# 4_PWM_MOSFETs.net
KiCad netlist of a schematic drawn in Altium Designer
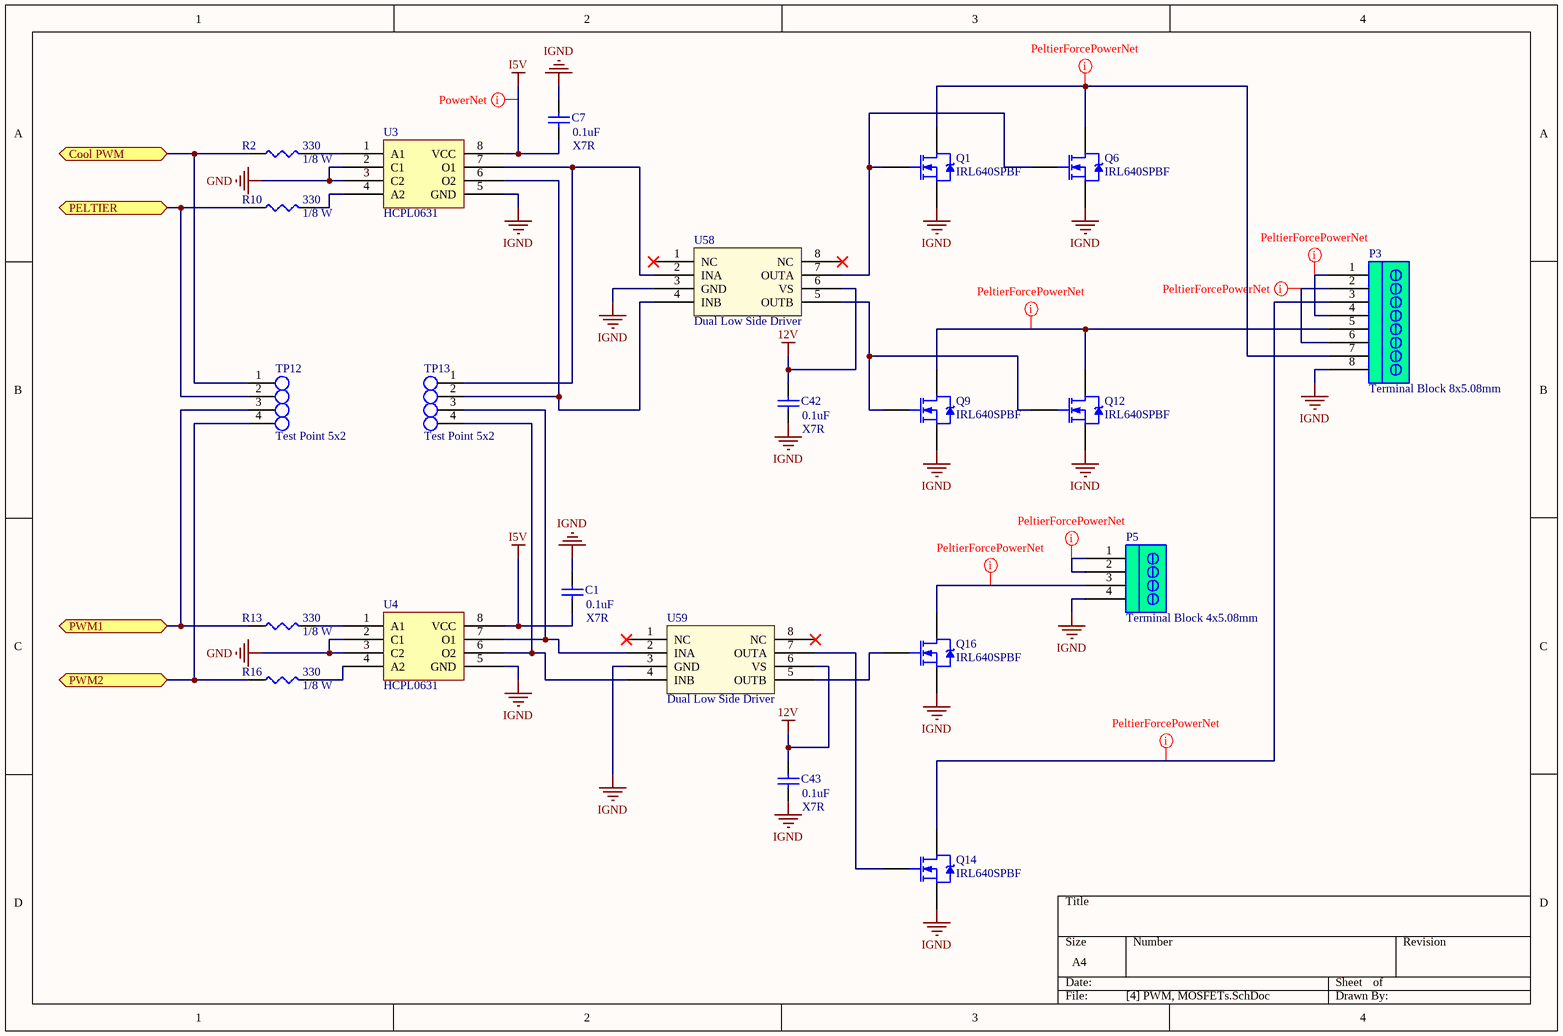
[diagram p0: [4] PWM, MOSFETs.SchDoc]

(export (version "E")
  (design (tool "Eeschema 10.0.6"))
  (components
    (comp (ref "C1")
      (value "0.1uF")
      (footprint "CAP0805")
      (description "Surface-mount ceramic multilayer capacitor")
      (fields (field (name "VOLTAGE") "50V") (field (name "TOLERANCE") "5%") (field (name "TYPE") "X7R"))
      (libsource (lib "Capacitors") (part "CAP0805 0.1uF X7R"))
    )
    (comp (ref "C7")
      (value "0.1uF")
      (footprint "CAP0805")
      (description "Surface-mount ceramic multilayer capacitor")
      (fields (field (name "VOLTAGE") "50V") (field (name "TOLERANCE") "5%") (field (name "TYPE") "X7R"))
      (libsource (lib "Capacitors") (part "CAP0805 0.1uF X7R"))
    )
    (comp (ref "C42")
      (value "0.1uF")
      (footprint "CAP0805")
      (description "Surface-mount ceramic multilayer capacitor")
      (fields (field (name "VOLTAGE") "50V") (field (name "TOLERANCE") "5%") (field (name "TYPE") "X7R"))
      (libsource (lib "Capacitors") (part "CAP0805 0.1uF X7R"))
    )
    (comp (ref "C43")
      (value "0.1uF")
      (footprint "CAP0805")
      (description "Surface-mount ceramic multilayer capacitor")
      (fields (field (name "VOLTAGE") "50V") (field (name "TOLERANCE") "5%") (field (name "TYPE") "X7R"))
      (libsource (lib "Capacitors") (part "CAP0805 0.1uF X7R"))
    )
    (comp (ref "P3")
      (value "Terminal Block 8x5.08mm")
      (footprint "SOCKET 8x5.08")
      (description "Terminal Block Socket Right Angle 8x5.08mm 2-Wall")
      (libsource (lib "IndustrialConnectors") (part "Socket_8x5.08_RA_2Wall"))
    )
    (comp (ref "P5")
      (value "Terminal Block 4x5.08mm")
      (footprint "Socket 4x5.08")
      (description "Terminal Block Socket Right Angle 4x5.08mm 2-Wall")
      (libsource (lib "IndustrialConnectors") (part "Socket_4x5.08_RA_2Wall"))
    )
    (comp (ref "Q1")
      (value "IRL640SPBF")
      (footprint "TO-263AB")
      (description "HEXFET N-Channel Power MOSFET")
      (fields (field (name "MANUFACTURER") "Vishay"))
      (libsource (lib "BJT") (part "IRL640SPBF"))
    )
    (comp (ref "Q6")
      (value "IRL640SPBF")
      (footprint "TO-263AB")
      (description "HEXFET N-Channel Power MOSFET")
      (fields (field (name "MANUFACTURER") "Vishay"))
      (libsource (lib "BJT") (part "IRL640SPBF"))
    )
    (comp (ref "Q9")
      (value "IRL640SPBF")
      (footprint "TO-263AB")
      (description "HEXFET N-Channel Power MOSFET")
      (fields (field (name "MANUFACTURER") "Vishay"))
      (libsource (lib "BJT") (part "IRL640SPBF"))
    )
    (comp (ref "Q12")
      (value "IRL640SPBF")
      (footprint "TO-263AB")
      (description "HEXFET N-Channel Power MOSFET")
      (fields (field (name "MANUFACTURER") "Vishay"))
      (libsource (lib "BJT") (part "IRL640SPBF"))
    )
    (comp (ref "Q14")
      (value "IRL640SPBF")
      (footprint "TO-263AB")
      (description "HEXFET N-Channel Power MOSFET")
      (fields (field (name "MANUFACTURER") "Vishay"))
      (libsource (lib "BJT") (part "IRL640SPBF"))
    )
    (comp (ref "Q16")
      (value "IRL640SPBF")
      (footprint "TO-263AB")
      (description "HEXFET N-Channel Power MOSFET")
      (fields (field (name "MANUFACTURER") "Vishay"))
      (libsource (lib "BJT") (part "IRL640SPBF"))
    )
    (comp (ref "R2")
      (value "330")
      (footprint "RES0805")
      (description "Think Film Chip resistor")
      (fields
        (field (name "TOLERANCE") "1%")
        (field (name "MANUFACTURER PART NUMBER") "RC0805FR-07330RL")
        (field (name "RATING") "1/8 W")
      )
      (libsource (lib "Resistors") (part "RES0805 330R 1%"))
    )
    (comp (ref "R10")
      (value "330")
      (footprint "RES0805")
      (description "Think Film Chip resistor")
      (fields
        (field (name "TOLERANCE") "1%")
        (field (name "MANUFACTURER PART NUMBER") "RC0805FR-07330RL")
        (field (name "RATING") "1/8 W")
      )
      (libsource (lib "Resistors") (part "RES0805 330R 1%"))
    )
    (comp (ref "R13")
      (value "330")
      (footprint "RES0805")
      (description "Think Film Chip resistor")
      (fields
        (field (name "TOLERANCE") "1%")
        (field (name "MANUFACTURER PART NUMBER") "RC0805FR-07330RL")
        (field (name "RATING") "1/8 W")
      )
      (libsource (lib "Resistors") (part "RES0805 330R 1%"))
    )
    (comp (ref "R16")
      (value "330")
      (footprint "RES0805")
      (description "Think Film Chip resistor")
      (fields
        (field (name "TOLERANCE") "1%")
        (field (name "MANUFACTURER PART NUMBER") "RC0805FR-07330RL")
        (field (name "RATING") "1/8 W")
      )
      (libsource (lib "Resistors") (part "RES0805 330R 1%"))
    )
    (comp (ref "TP12")
      (value "Test Point 5x2")
      (footprint "PG-1.5-13.5-4P-2.54PH")
      (libsource (lib "Connectors") (part "PG-1.5-13.5-4P-2.54PH"))
    )
    (comp (ref "TP13")
      (value "Test Point 5x2")
      (footprint "PG-1.5-13.5-4P-2.54PH")
      (libsource (lib "Connectors") (part "PG-1.5-13.5-4P-2.54PH"))
    )
    (comp (ref "U3")
      (value "HCPL0631")
      (footprint "SOIC8")
      (description "2-channel opto-coupler")
      (libsource (lib "Avago Optocouplers") (part "HCPL0631"))
    )
    (comp (ref "U4")
      (value "HCPL0631")
      (footprint "SOIC8")
      (description "2-channel opto-coupler")
      (libsource (lib "Avago Optocouplers") (part "HCPL0631"))
    )
    (comp (ref "U58")
      (value "Dual Low Side Driver")
      (footprint "SOIC8")
      (description "IR MOSFET Dual Low Side Driver")
      (fields (field (name "MANUFACTURER") "IR") (field (name "MANUFACTURER PART NUMBER") "IR4426"))
      (libsource (lib "IR MOSFET Driver") (part "IR4426"))
    )
    (comp (ref "U59")
      (value "Dual Low Side Driver")
      (footprint "SOIC8")
      (description "IR MOSFET Dual Low Side Driver")
      (fields (field (name "MANUFACTURER") "IR") (field (name "MANUFACTURER PART NUMBER") "IR4426"))
      (libsource (lib "IR MOSFET Driver") (part "IR4426"))
    )
  )
  (nets
    (net (code "1") (name "/Cool PWM") (class "Default")
      (node (ref "R2") (pin "1") (pintype "passive"))
      (node (ref "TP12") (pin "1") (pinfunction "1_1") (pintype "passive"))
    )
    (net (code "2") (name "/PELTIER") (class "Default")
      (node (ref "R10") (pin "1") (pintype "passive"))
      (node (ref "TP12") (pin "2") (pinfunction "2_2") (pintype "passive"))
    )
    (net (code "3") (name "/PWM1") (class "Default")
      (node (ref "R13") (pin "1") (pintype "passive"))
      (node (ref "TP12") (pin "3") (pinfunction "3_3") (pintype "passive"))
    )
    (net (code "4") (name "/PWM2") (class "Default")
      (node (ref "R16") (pin "1") (pintype "passive"))
      (node (ref "TP12") (pin "4") (pinfunction "4_4") (pintype "passive"))
    )
    (net (code "5") (name "12V") (class "Default")
      (node (ref "C42") (pin "2") (pinfunction "2_2") (pintype "passive"))
      (node (ref "C43") (pin "2") (pinfunction "2_2") (pintype "passive"))
      (node (ref "U58") (pin "6") (pinfunction "VS_6") (pintype "passive"))
      (node (ref "U59") (pin "6") (pinfunction "VS_6") (pintype "passive"))
    )
    (net (code "6") (name "GND") (class "Default")
      (node (ref "U3") (pin "2") (pinfunction "C1_2") (pintype "passive"))
      (node (ref "U3") (pin "3") (pinfunction "C2_3") (pintype "passive"))
      (node (ref "U4") (pin "2") (pinfunction "C1_2") (pintype "passive"))
      (node (ref "U4") (pin "3") (pinfunction "C2_3") (pintype "passive"))
    )
    (net (code "7") (name "I5V") (class "Default")
      (node (ref "C1") (pin "1") (pinfunction "1_1") (pintype "passive"))
      (node (ref "C7") (pin "1") (pinfunction "1_1") (pintype "passive"))
      (node (ref "U3") (pin "8") (pinfunction "VCC_8") (pintype "passive"))
      (node (ref "U4") (pin "8") (pinfunction "VCC_8") (pintype "passive"))
    )
    (net (code "8") (name "IGND") (class "Default")
      (node (ref "C1") (pin "2") (pinfunction "2_2") (pintype "passive"))
      (node (ref "C42") (pin "1") (pinfunction "1_1") (pintype "passive"))
      (node (ref "C43") (pin "1") (pinfunction "1_1") (pintype "passive"))
      (node (ref "C7") (pin "2") (pinfunction "2_2") (pintype "passive"))
      (node (ref "P3") (pin "8") (pintype "passive"))
      (node (ref "P5") (pin "4") (pintype "passive"))
      (node (ref "Q1") (pin "3") (pinfunction "S_3") (pintype "passive"))
      (node (ref "Q12") (pin "3") (pinfunction "S_3") (pintype "passive"))
      (node (ref "Q14") (pin "3") (pinfunction "S_3") (pintype "passive"))
      (node (ref "Q16") (pin "3") (pinfunction "S_3") (pintype "passive"))
      (node (ref "Q6") (pin "3") (pinfunction "S_3") (pintype "passive"))
      (node (ref "Q9") (pin "3") (pinfunction "S_3") (pintype "passive"))
      (node (ref "U3") (pin "5") (pinfunction "GND_5") (pintype "passive"))
      (node (ref "U4") (pin "5") (pinfunction "GND_5") (pintype "passive"))
      (node (ref "U58") (pin "3") (pinfunction "GND_3") (pintype "passive"))
      (node (ref "U59") (pin "3") (pinfunction "GND_3") (pintype "passive"))
    )
    (net (code "9") (name "Net-(P3-Pad1)") (class "Default")
      (node (ref "P3") (pin "1") (pintype "passive"))
      (node (ref "P3") (pin "4") (pintype "passive"))
    )
    (net (code "10") (name "Net-(P3-Pad2)") (class "Default")
      (node (ref "P3") (pin "2") (pintype "passive"))
      (node (ref "P3") (pin "6") (pintype "passive"))
    )
    (net (code "11") (name "Net-(P5-Pad1)") (class "Default")
      (node (ref "P5") (pin "1") (pintype "passive"))
      (node (ref "P5") (pin "2") (pintype "passive"))
    )
    (net (code "12") (name "Net-(Q1-D)") (class "Default")
      (node (ref "P3") (pin "7") (pintype "passive"))
      (node (ref "Q1") (pin "2") (pinfunction "D_2") (pintype "passive"))
      (node (ref "Q6") (pin "2") (pinfunction "D_2") (pintype "passive"))
    )
    (net (code "13") (name "Net-(Q1-G)") (class "Default")
      (node (ref "Q1") (pin "1") (pinfunction "G_1") (pintype "passive"))
      (node (ref "Q6") (pin "1") (pinfunction "G_1") (pintype "passive"))
      (node (ref "U58") (pin "7") (pinfunction "OUTA_7") (pintype "passive"))
    )
    (net (code "14") (name "Net-(Q12-D)") (class "Default")
      (node (ref "P3") (pin "5") (pintype "passive"))
      (node (ref "Q12") (pin "2") (pinfunction "D_2") (pintype "passive"))
      (node (ref "Q9") (pin "2") (pinfunction "D_2") (pintype "passive"))
    )
    (net (code "15") (name "Net-(Q12-G)") (class "Default")
      (node (ref "Q12") (pin "1") (pinfunction "G_1") (pintype "passive"))
      (node (ref "Q9") (pin "1") (pinfunction "G_1") (pintype "passive"))
      (node (ref "U58") (pin "5") (pinfunction "OUTB_5") (pintype "passive"))
    )
    (net (code "16") (name "Net-(Q14-D)") (class "Default")
      (node (ref "P3") (pin "3") (pintype "passive"))
      (node (ref "Q14") (pin "2") (pinfunction "D_2") (pintype "passive"))
    )
    (net (code "17") (name "Net-(Q14-G)") (class "Default")
      (node (ref "Q14") (pin "1") (pinfunction "G_1") (pintype "passive"))
      (node (ref "U59") (pin "7") (pinfunction "OUTA_7") (pintype "passive"))
    )
    (net (code "18") (name "Net-(Q16-D)") (class "Default")
      (node (ref "P5") (pin "3") (pintype "passive"))
      (node (ref "Q16") (pin "2") (pinfunction "D_2") (pintype "passive"))
    )
    (net (code "19") (name "Net-(Q16-G)") (class "Default")
      (node (ref "Q16") (pin "1") (pinfunction "G_1") (pintype "passive"))
      (node (ref "U59") (pin "5") (pinfunction "OUTB_5") (pintype "passive"))
    )
    (net (code "20") (name "Net-(U3-A1)") (class "Default")
      (node (ref "R2") (pin "2") (pintype "passive"))
      (node (ref "U3") (pin "1") (pinfunction "A1_1") (pintype "passive"))
    )
    (net (code "21") (name "Net-(U3-A2)") (class "Default")
      (node (ref "R10") (pin "2") (pintype "passive"))
      (node (ref "U3") (pin "4") (pinfunction "A2_4") (pintype "passive"))
    )
    (net (code "22") (name "Net-(U3-O1)") (class "Default")
      (node (ref "TP13") (pin "1") (pinfunction "1_1") (pintype "passive"))
      (node (ref "U3") (pin "7") (pinfunction "O1_7") (pintype "passive"))
      (node (ref "U58") (pin "2") (pinfunction "INA_2") (pintype "passive"))
    )
    (net (code "23") (name "Net-(U3-O2)") (class "Default")
      (node (ref "TP13") (pin "2") (pinfunction "2_2") (pintype "passive"))
      (node (ref "U3") (pin "6") (pinfunction "O2_6") (pintype "passive"))
      (node (ref "U58") (pin "4") (pinfunction "INB_4") (pintype "passive"))
    )
    (net (code "24") (name "Net-(U4-A1)") (class "Default")
      (node (ref "R13") (pin "2") (pintype "passive"))
      (node (ref "U4") (pin "1") (pinfunction "A1_1") (pintype "passive"))
    )
    (net (code "25") (name "Net-(U4-A2)") (class "Default")
      (node (ref "R16") (pin "2") (pintype "passive"))
      (node (ref "U4") (pin "4") (pinfunction "A2_4") (pintype "passive"))
    )
    (net (code "26") (name "Net-(U4-O1)") (class "Default")
      (node (ref "TP13") (pin "3") (pinfunction "3_3") (pintype "passive"))
      (node (ref "U4") (pin "7") (pinfunction "O1_7") (pintype "passive"))
      (node (ref "U59") (pin "2") (pinfunction "INA_2") (pintype "passive"))
    )
    (net (code "27") (name "Net-(U4-O2)") (class "Default")
      (node (ref "TP13") (pin "4") (pinfunction "4_4") (pintype "passive"))
      (node (ref "U4") (pin "6") (pinfunction "O2_6") (pintype "passive"))
      (node (ref "U59") (pin "4") (pinfunction "INB_4") (pintype "passive"))
    )
    (net (code "28") (name "unconnected-(U58-NC-Pad1)") (class "Default")
      (node (ref "U58") (pin "1") (pinfunction "NC_1") (pintype "passive+no_connect"))
    )
    (net (code "29") (name "unconnected-(U58-NC-Pad8)") (class "Default")
      (node (ref "U58") (pin "8") (pinfunction "NC_8") (pintype "passive+no_connect"))
    )
    (net (code "30") (name "unconnected-(U59-NC-Pad1)") (class "Default")
      (node (ref "U59") (pin "1") (pinfunction "NC_1") (pintype "passive+no_connect"))
    )
    (net (code "31") (name "unconnected-(U59-NC-Pad8)") (class "Default")
      (node (ref "U59") (pin "8") (pinfunction "NC_8") (pintype "passive+no_connect"))
    )
  )
)
